# Brain1portA.net
KiCad netlist of a schematic drawn in EAGLE
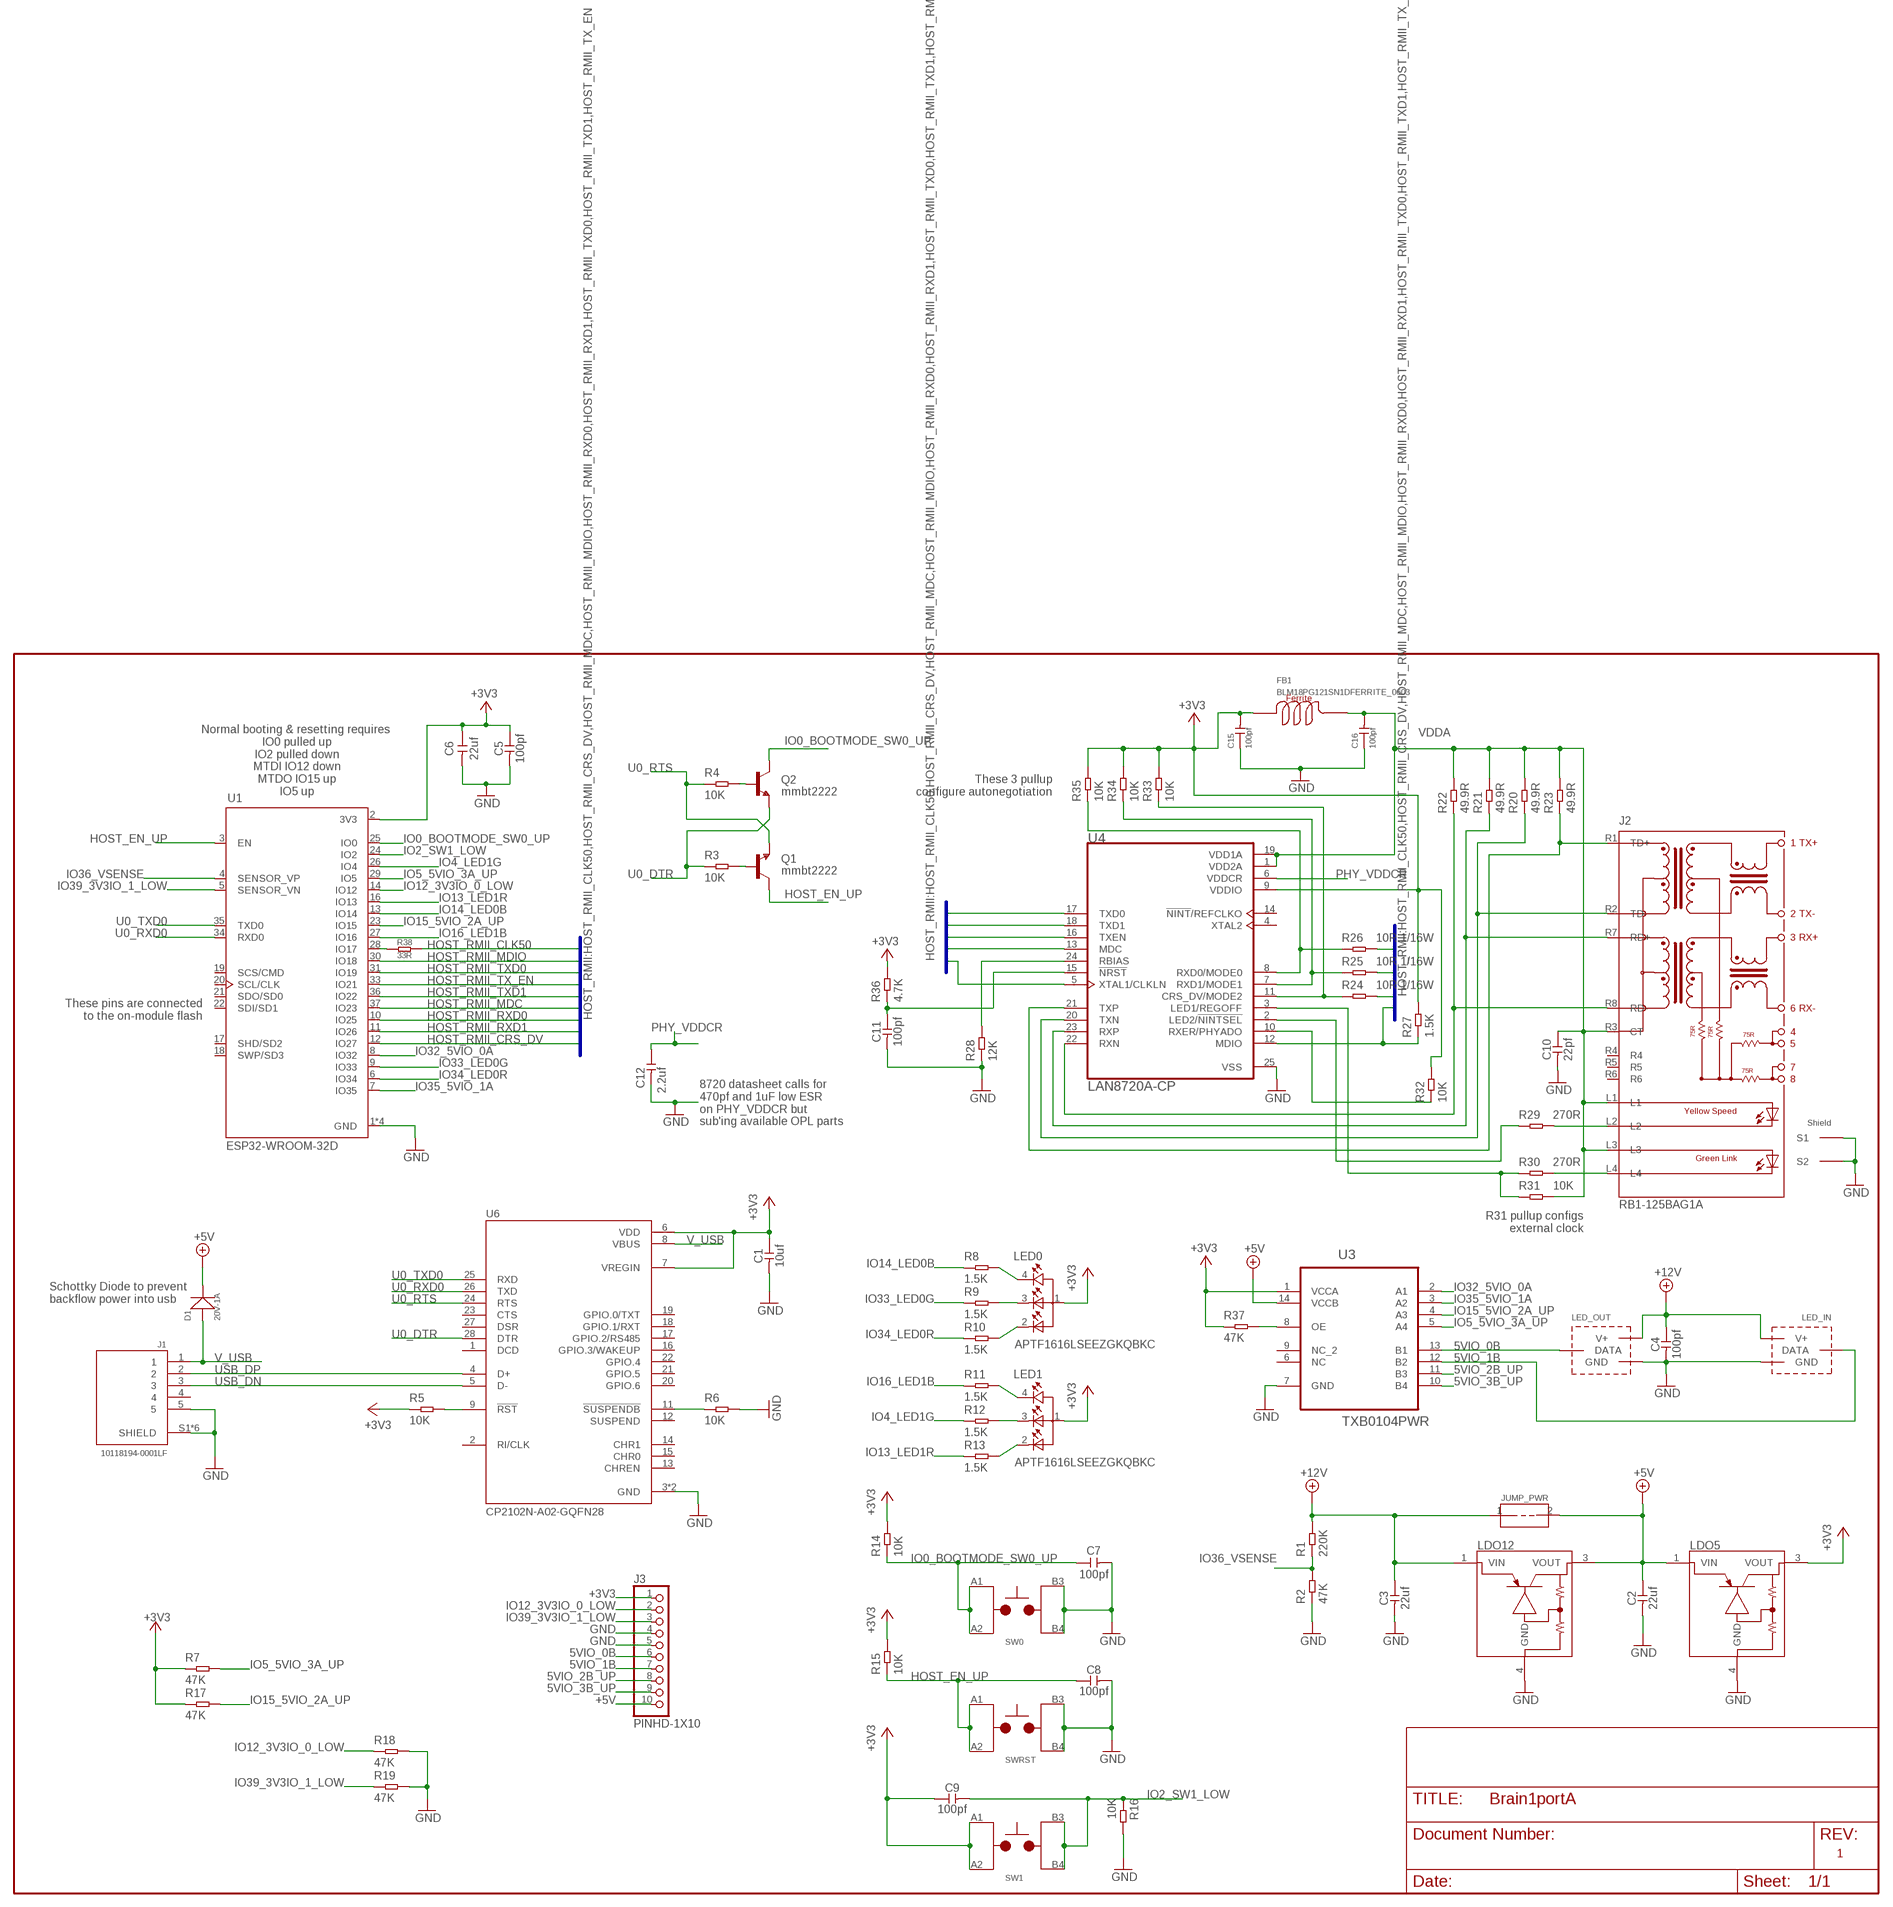
[diagram p0: schematic, sheet 1]

(export (version "E")
  (design (tool "Eeschema 10.0.6"))
  (components
    (comp (ref "C1")
      (value "10uf")
      (footprint "eagle-import:C0402")
      (fields (field (name "MPN") "CC0402MRX5R5BB106"))
      (libsource (lib "eagle-import") (part "CERAMIC-10UF-6.3V-20%-X5R(0402)"))
    )
    (comp (ref "C2")
      (value "22uf")
      (footprint "eagle-import:C0805")
      (fields (field (name "MPN") "CC0805MKX5R5BB226"))
      (libsource (lib "eagle-import") (part "CERAMIC-22UF-6.3V-20%-X5R(0805)"))
    )
    (comp (ref "C3")
      (value "22uf")
      (footprint "eagle-import:C0805")
      (fields (field (name "MPN") "CC0805MKX5R5BB226"))
      (libsource (lib "eagle-import") (part "CERAMIC-22UF-6.3V-20%-X5R(0805)"))
    )
    (comp (ref "C4")
      (value "100pf")
      (footprint "eagle-import:C0402")
      (fields (field (name "MPN") "CC0402JRNPO9BN101"))
      (libsource (lib "eagle-import") (part "CERAMIC-100PF-50V-5%-NPO(0402)"))
    )
    (comp (ref "C5")
      (value "100pf")
      (footprint "eagle-import:C0402")
      (fields (field (name "MPN") "CC0402JRNPO9BN101"))
      (libsource (lib "eagle-import") (part "CERAMIC-100PF-50V-5%-NPO(0402)"))
    )
    (comp (ref "C6")
      (value "22uf")
      (footprint "eagle-import:C0805")
      (fields (field (name "MPN") "CC0805MKX5R5BB226"))
      (libsource (lib "eagle-import") (part "CERAMIC-22UF-6.3V-20%-X5R(0805)"))
    )
    (comp (ref "C7")
      (value "100pf")
      (footprint "eagle-import:C0402")
      (fields (field (name "MPN") "CC0402JRNPO9BN101"))
      (libsource (lib "eagle-import") (part "CERAMIC-100PF-50V-5%-NPO(0402)"))
    )
    (comp (ref "C8")
      (value "100pf")
      (footprint "eagle-import:C0402")
      (fields (field (name "MPN") "CC0402JRNPO9BN101"))
      (libsource (lib "eagle-import") (part "CERAMIC-100PF-50V-5%-NPO(0402)"))
    )
    (comp (ref "C9")
      (value "100pf")
      (footprint "eagle-import:C0402")
      (fields (field (name "MPN") "CC0402JRNPO9BN101"))
      (libsource (lib "eagle-import") (part "CERAMIC-100PF-50V-5%-NPO(0402)"))
    )
    (comp (ref "C10")
      (value "22pf")
      (footprint "eagle-import:C0402")
      (fields (field (name "MPN") "CC0402JRNPO9BN220"))
      (libsource (lib "eagle-import") (part "CERAMIC-22PF-50V-5%-NPO(0402)"))
    )
    (comp (ref "C11")
      (value "100pf")
      (footprint "eagle-import:C0402")
      (fields (field (name "MPN") "CC0402JRNPO9BN101"))
      (libsource (lib "eagle-import") (part "CERAMIC-100PF-50V-5%-NPO(0402)"))
    )
    (comp (ref "C12")
      (value "2.2uf")
      (footprint "eagle-import:C0603")
      (fields (field (name "MPN") "CC0603KRX7R6BB225"))
      (libsource (lib "eagle-import") (part "CERAMIC-2.2UF-10V-10%-X7R(0603)"))
    )
    (comp (ref "C15")
      (value "100pf")
      (footprint "eagle-import:C0402")
      (fields (field (name "MPN") "CC0402JRNPO9BN101"))
      (libsource (lib "eagle-import") (part "CERAMIC-100PF-50V-5%-NPO(0402)"))
    )
    (comp (ref "C16")
      (value "100pf")
      (footprint "eagle-import:C0402")
      (fields (field (name "MPN") "CC0402JRNPO9BN101"))
      (libsource (lib "eagle-import") (part "CERAMIC-100PF-50V-5%-NPO(0402)"))
    )
    (comp (ref "D1")
      (value "20V-1A")
      (footprint "eagle-import:SOD-123")
      (fields (field (name "MPN") "B5819W"))
      (libsource (lib "eagle-import") (part "SMD-DIODE-SCHOTTKY-20V-1A(SOD-123)"))
    )
    (comp (ref "FB1")
      (value "BLM18PG121SN1DFERRITE_0603")
      (footprint "eagle-import:L0603")
      (libsource (lib "eagle-import") (part "BLM18PG121SN1DFERRITE_0603"))
    )
    (comp (ref "J1")
      (value "10118194-0001LF")
      (footprint "eagle-import:AMPHENOL_10118194-0001LF")
      (fields (field (name "DIGI-KEY_PART_NUMBER") "609-4618-1-ND") (field (name "MF") "Amphenol ICC"))
      (libsource (lib "eagle-import") (part "10118194-0001LF"))
    )
    (comp (ref "J2")
      (value "RB1-125BAG1A")
      (footprint "eagle-import:WIZNET_RB1-125BAG1A")
      (libsource (lib "eagle-import") (part "RB1-125BAG1A"))
    )
    (comp (ref "J3")
      (value "PINHD-1X10")
      (footprint "eagle-import:1X10-BIG")
      (libsource (lib "eagle-import") (part "PINHD-1X10"))
    )
    (comp (ref "JUMP_PWR")
      (value "PWR_SUPPLY_SHORT050_DRILLED")
      (footprint "eagle-import:SHORT_050_DRILLED")
      (libsource (lib "eagle-import") (part "PWR_SUPPLY_SHORT050_DRILLED"))
    )
    (comp (ref "LDO5")
      (value "NCP5501DPAK3")
      (footprint "eagle-import:TO229P990X238-3")
      (libsource (lib "eagle-import") (part "NCP5501DPAK3"))
    )
    (comp (ref "LDO12")
      (value "NCP5501DPAK3")
      (footprint "eagle-import:TO229P990X238-3")
      (libsource (lib "eagle-import") (part "NCP5501DPAK3"))
    )
    (comp (ref "LED0")
      (value "APTF1616LSEEZGKQBKC")
      (footprint "eagle-import:LEDSC160X160X070-4N")
      (fields (field (name "MF") "Kingbright"))
      (libsource (lib "eagle-import") (part "APTF1616LSEEZGKQBKC"))
    )
    (comp (ref "LED1")
      (value "APTF1616LSEEZGKQBKC")
      (footprint "eagle-import:LEDSC160X160X070-4N")
      (fields (field (name "MF") "Kingbright"))
      (libsource (lib "eagle-import") (part "APTF1616LSEEZGKQBKC"))
    )
    (comp (ref "LED_IN")
      (value "3WAY_LED_CONWIRES")
      (footprint "eagle-import:3WAY_LED_WIRES")
      (libsource (lib "eagle-import") (part "3WAY_LED_CONWIRES"))
    )
    (comp (ref "LED_OUT")
      (value "3WAY_LED_CONWIRES")
      (footprint "eagle-import:3WAY_LED_WIRES")
      (libsource (lib "eagle-import") (part "3WAY_LED_CONWIRES"))
    )
    (comp (ref "Q1")
      (value "mmbt2222")
      (footprint "eagle-import:SOT23-BEC")
      (libsource (lib "eagle-import") (part "-NPN-SOT23-BECMMBT2222ALT1"))
    )
    (comp (ref "Q2")
      (value "mmbt2222")
      (footprint "eagle-import:SOT23-BEC")
      (libsource (lib "eagle-import") (part "-NPN-SOT23-BECMMBT2222ALT1"))
    )
    (comp (ref "R1")
      (value "220K")
      (footprint "eagle-import:R0402")
      (fields (field (name "MPN") "RC0402JR-070RL"))
      (libsource (lib "eagle-import") (part "SMD-RES-220K-5%-1/16W(0402)"))
    )
    (comp (ref "R2")
      (value "47K")
      (footprint "eagle-import:R0402")
      (fields (field (name "MPN") "RC0402JR-0747KL"))
      (libsource (lib "eagle-import") (part "SMD-RES-47K-5%-1/16W(0402)"))
    )
    (comp (ref "R3")
      (value "10K")
      (footprint "eagle-import:R0402")
      (fields (field (name "MPN") "RC0402JR-0710KL"))
      (libsource (lib "eagle-import") (part "SMD-RES-10K-5%-1/(0402)"))
    )
    (comp (ref "R4")
      (value "10K")
      (footprint "eagle-import:R0402")
      (fields (field (name "MPN") "RC0402JR-0710KL"))
      (libsource (lib "eagle-import") (part "SMD-RES-10K-5%-1/(0402)"))
    )
    (comp (ref "R5")
      (value "10K")
      (footprint "eagle-import:R0402")
      (fields (field (name "MPN") "RC0402JR-0710KL"))
      (libsource (lib "eagle-import") (part "SMD-RES-10K-5%-1/(0402)"))
    )
    (comp (ref "R6")
      (value "10K")
      (footprint "eagle-import:R0402")
      (fields (field (name "MPN") "RC0402JR-0710KL"))
      (libsource (lib "eagle-import") (part "SMD-RES-10K-5%-1/(0402)"))
    )
    (comp (ref "R7")
      (value "47K")
      (footprint "eagle-import:R0402")
      (fields (field (name "MPN") "RC0402JR-0747KL"))
      (libsource (lib "eagle-import") (part "SMD-RES-47K-5%-1/16W(0402)"))
    )
    (comp (ref "R8")
      (value "1.5K")
      (footprint "eagle-import:R0402")
      (fields (field (name "MPN") "RC0402JR-071K5L"))
      (libsource (lib "eagle-import") (part "SMD-RES-1.5K-5%-1/16W(0402)"))
    )
    (comp (ref "R9")
      (value "1.5K")
      (footprint "eagle-import:R0402")
      (fields (field (name "MPN") "RC0402JR-071K5L"))
      (libsource (lib "eagle-import") (part "SMD-RES-1.5K-5%-1/16W(0402)"))
    )
    (comp (ref "R10")
      (value "1.5K")
      (footprint "eagle-import:R0402")
      (fields (field (name "MPN") "RC0402JR-071K5L"))
      (libsource (lib "eagle-import") (part "SMD-RES-1.5K-5%-1/16W(0402)"))
    )
    (comp (ref "R11")
      (value "1.5K")
      (footprint "eagle-import:R0402")
      (fields (field (name "MPN") "RC0402JR-071K5L"))
      (libsource (lib "eagle-import") (part "SMD-RES-1.5K-5%-1/16W(0402)"))
    )
    (comp (ref "R12")
      (value "1.5K")
      (footprint "eagle-import:R0402")
      (fields (field (name "MPN") "RC0402JR-071K5L"))
      (libsource (lib "eagle-import") (part "SMD-RES-1.5K-5%-1/16W(0402)"))
    )
    (comp (ref "R13")
      (value "1.5K")
      (footprint "eagle-import:R0402")
      (fields (field (name "MPN") "RC0402JR-071K5L"))
      (libsource (lib "eagle-import") (part "SMD-RES-1.5K-5%-1/16W(0402)"))
    )
    (comp (ref "R14")
      (value "10K")
      (footprint "eagle-import:R0402")
      (fields (field (name "MPN") "RC0402JR-0710KL"))
      (libsource (lib "eagle-import") (part "SMD-RES-10K-5%-1/(0402)"))
    )
    (comp (ref "R15")
      (value "10K")
      (footprint "eagle-import:R0402")
      (fields (field (name "MPN") "RC0402JR-0710KL"))
      (libsource (lib "eagle-import") (part "SMD-RES-10K-5%-1/(0402)"))
    )
    (comp (ref "R16")
      (value "10K")
      (footprint "eagle-import:R0402")
      (fields (field (name "MPN") "RC0402JR-0710KL"))
      (libsource (lib "eagle-import") (part "SMD-RES-10K-5%-1/(0402)"))
    )
    (comp (ref "R17")
      (value "47K")
      (footprint "eagle-import:R0402")
      (fields (field (name "MPN") "RC0402JR-0747KL"))
      (libsource (lib "eagle-import") (part "SMD-RES-47K-5%-1/16W(0402)"))
    )
    (comp (ref "R18")
      (value "47K")
      (footprint "eagle-import:R0402")
      (fields (field (name "MPN") "RC0402JR-0747KL"))
      (libsource (lib "eagle-import") (part "SMD-RES-47K-5%-1/16W(0402)"))
    )
    (comp (ref "R19")
      (value "47K")
      (footprint "eagle-import:R0402")
      (fields (field (name "MPN") "RC0402JR-0747KL"))
      (libsource (lib "eagle-import") (part "SMD-RES-47K-5%-1/16W(0402)"))
    )
    (comp (ref "R20")
      (value "49.9R")
      (footprint "eagle-import:R0402")
      (fields (field (name "MPN") "RC0402FR-0749R9L"))
      (libsource (lib "eagle-import") (part "SMD-RES-49.9R-1%-1/16W(0402)"))
    )
    (comp (ref "R21")
      (value "49.9R")
      (footprint "eagle-import:R0402")
      (fields (field (name "MPN") "RC0402FR-0749R9L"))
      (libsource (lib "eagle-import") (part "SMD-RES-49.9R-1%-1/16W(0402)"))
    )
    (comp (ref "R22")
      (value "49.9R")
      (footprint "eagle-import:R0402")
      (fields (field (name "MPN") "RC0402FR-0749R9L"))
      (libsource (lib "eagle-import") (part "SMD-RES-49.9R-1%-1/16W(0402)"))
    )
    (comp (ref "R23")
      (value "49.9R")
      (footprint "eagle-import:R0402")
      (fields (field (name "MPN") "RC0402FR-0749R9L"))
      (libsource (lib "eagle-import") (part "SMD-RES-49.9R-1%-1/16W(0402)"))
    )
    (comp (ref "R24")
      (value "10R 1/16W")
      (footprint "eagle-import:R0402")
      (fields (field (name "MPN") "RC0402JR-0710RL"))
      (libsource (lib "eagle-import") (part "SMD-RES-10R-5%-1/16W(0402)"))
    )
    (comp (ref "R25")
      (value "10R 1/16W")
      (footprint "eagle-import:R0402")
      (fields (field (name "MPN") "RC0402JR-0710RL"))
      (libsource (lib "eagle-import") (part "SMD-RES-10R-5%-1/16W(0402)"))
    )
    (comp (ref "R26")
      (value "10R 1/16W")
      (footprint "eagle-import:R0402")
      (fields (field (name "MPN") "RC0402JR-0710RL"))
      (libsource (lib "eagle-import") (part "SMD-RES-10R-5%-1/16W(0402)"))
    )
    (comp (ref "R27")
      (value "1.5K")
      (footprint "eagle-import:R0402")
      (fields (field (name "MPN") "RC0402JR-071K5L"))
      (libsource (lib "eagle-import") (part "SMD-RES-1.5K-5%-1/16W(0402)"))
    )
    (comp (ref "R28")
      (value "12K")
      (footprint "eagle-import:R0402")
      (fields (field (name "MPN") "RC0402JR-070RL"))
      (libsource (lib "eagle-import") (part "SMD-RES-12K-1%-1/16W(0402)"))
    )
    (comp (ref "R29")
      (value "270R")
      (footprint "eagle-import:R0402")
      (fields (field (name "MPN") "RC0402JR-070RL"))
      (libsource (lib "eagle-import") (part "SMD-RES-270R-1%-1/16W(0402)"))
    )
    (comp (ref "R30")
      (value "270R")
      (footprint "eagle-import:R0402")
      (fields (field (name "MPN") "RC0402JR-070RL"))
      (libsource (lib "eagle-import") (part "SMD-RES-270R-1%-1/16W(0402)"))
    )
    (comp (ref "R31")
      (value "10K")
      (footprint "eagle-import:R0402")
      (fields (field (name "MPN") "RC0402JR-0710KL"))
      (libsource (lib "eagle-import") (part "SMD-RES-10K-5%-1/(0402)"))
    )
    (comp (ref "R32")
      (value "10K")
      (footprint "eagle-import:R0402")
      (fields (field (name "MPN") "RC0402JR-0710KL"))
      (libsource (lib "eagle-import") (part "SMD-RES-10K-5%-1/(0402)"))
    )
    (comp (ref "R33")
      (value "10K")
      (footprint "eagle-import:R0402")
      (fields (field (name "MPN") "RC0402JR-0710KL"))
      (libsource (lib "eagle-import") (part "SMD-RES-10K-5%-1/(0402)"))
    )
    (comp (ref "R34")
      (value "10K")
      (footprint "eagle-import:R0402")
      (fields (field (name "MPN") "RC0402JR-0710KL"))
      (libsource (lib "eagle-import") (part "SMD-RES-10K-5%-1/(0402)"))
    )
    (comp (ref "R35")
      (value "10K")
      (footprint "eagle-import:R0402")
      (fields (field (name "MPN") "RC0402JR-0710KL"))
      (libsource (lib "eagle-import") (part "SMD-RES-10K-5%-1/(0402)"))
    )
    (comp (ref "R36")
      (value "4.7K")
      (footprint "eagle-import:R0402")
      (fields (field (name "MPN") "RC0402JR-074K7L"))
      (libsource (lib "eagle-import") (part "SMD-RES-4.7K-5%-1/16W(0402)"))
    )
    (comp (ref "R37")
      (value "47K")
      (footprint "eagle-import:R0402")
      (fields (field (name "MPN") "RC0402JR-0747KL"))
      (libsource (lib "eagle-import") (part "SMD-RES-47K-5%-1/16W(0402)"))
    )
    (comp (ref "R38")
      (value "33R")
      (footprint "eagle-import:R0603")
      (fields (field (name "MPN") "RC0603FR-071K5L"))
      (libsource (lib "eagle-import") (part "SMD-RES-33R-5%-1/10W(0603)"))
    )
    (comp (ref "SW0")
      (value "TL3301T3301SWITCH")
      (footprint "eagle-import:SW-4")
      (libsource (lib "eagle-import") (part "TL3301T3301SWITCH"))
    )
    (comp (ref "SW1")
      (value "TL3301T3301SWITCH")
      (footprint "eagle-import:SW-4")
      (libsource (lib "eagle-import") (part "TL3301T3301SWITCH"))
    )
    (comp (ref "SWRST")
      (value "TL3301T3301SWITCH")
      (footprint "eagle-import:SW-4")
      (libsource (lib "eagle-import") (part "TL3301T3301SWITCH"))
    )
    (comp (ref "U1")
      (value "ESP32-WROOM-32D")
      (footprint "eagle-import:MODULE_ESP32-WROOM-32D")
      (fields (field (name "DIGI-KEY_PART_NUMBER") "1904-1023-1-ND") (field (name "MF") "Espressif Systems"))
      (libsource (lib "eagle-import") (part "ESP32-WROOM-32D"))
    )
    (comp (ref "U3")
      (value "TXB0104PWR")
      (footprint "eagle-import:SOP65P640X120-14N")
      (fields (field (name "MF") "Texas Instruments"))
      (libsource (lib "eagle-import") (part "TXB0104PWR"))
    )
    (comp (ref "U4")
      (value "LAN8720A-CP")
      (footprint "eagle-import:QFN50P400X400X100-25N")
      (fields (field (name "DIGI-KEY_PART_NUMBER") "638-1080-ND") (field (name "MF") "Microchip"))
      (libsource (lib "eagle-import") (part "LAN8720A-CP"))
    )
    (comp (ref "U6")
      (value "CP2102N-A02-GQFN28")
      (footprint "eagle-import:QFN50P500X500X80-29N")
      (fields (field (name "MF") "Silicon Labs") (field (name "MP") "CP2102N-A01-GQFN28"))
      (libsource (lib "eagle-import") (part "CP2102N-A01-GQFN28"))
    )
  )
  (nets
    (net (code "2") (name "+3V3") (class "Default")
      (node (ref "C1") (pin "1") (pinfunction "1_1") (pintype "passive"))
      (node (ref "C15") (pin "2") (pinfunction "2_2") (pintype "passive"))
      (node (ref "C5") (pin "1") (pinfunction "1_1") (pintype "passive"))
      (node (ref "C6") (pin "1") (pinfunction "1_1") (pintype "passive"))
      (node (ref "C9") (pin "1") (pinfunction "1_1") (pintype "passive"))
      (node (ref "FB1") (pin "1") (pinfunction "P$1_1") (pintype "bidirectional"))
      (node (ref "J3") (pin "1") (pinfunction "1_1") (pintype "passive"))
      (node (ref "LDO5") (pin "3") (pinfunction "VOUT_3") (pintype "power_in"))
      (node (ref "LED0") (pin "1") (pinfunction "1_1") (pintype "passive"))
      (node (ref "LED1") (pin "1") (pinfunction "1_1") (pintype "passive"))
      (node (ref "R14") (pin "2") (pinfunction "2_2") (pintype "passive"))
      (node (ref "R15") (pin "2") (pinfunction "2_2") (pintype "passive"))
      (node (ref "R17") (pin "1") (pinfunction "1_1") (pintype "passive"))
      (node (ref "R27") (pin "2") (pinfunction "2_2") (pintype "passive"))
      (node (ref "R32") (pin "2") (pinfunction "2_2") (pintype "passive"))
      (node (ref "R33") (pin "2") (pinfunction "2_2") (pintype "passive"))
      (node (ref "R34") (pin "2") (pinfunction "2_2") (pintype "passive"))
      (node (ref "R35") (pin "2") (pinfunction "2_2") (pintype "passive"))
      (node (ref "R36") (pin "2") (pinfunction "2_2") (pintype "passive"))
      (node (ref "R37") (pin "1") (pinfunction "1_1") (pintype "passive"))
      (node (ref "R5") (pin "1") (pinfunction "1_1") (pintype "passive"))
      (node (ref "R7") (pin "1") (pinfunction "1_1") (pintype "passive"))
      (node (ref "SW1") (pin "A1") (pinfunction "1_A1") (pintype "bidirectional"))
      (node (ref "SW1") (pin "A2") (pinfunction "2_A2") (pintype "bidirectional"))
      (node (ref "U1") (pin "2") (pinfunction "3V3_2") (pintype "power_in"))
      (node (ref "U3") (pin "1") (pinfunction "VCCA_1") (pintype "power_in"))
      (node (ref "U4") (pin "9") (pinfunction "VDDIO_9") (pintype "power_in"))
      (node (ref "U6") (pin "6") (pinfunction "VDD_6") (pintype "power_in"))
      (node (ref "U6") (pin "7") (pinfunction "VREGIN_7") (pintype "power_in"))
    )
    (net (code "3") (name "+5V") (class "Default")
      (node (ref "C2") (pin "1") (pinfunction "1_1") (pintype "passive"))
      (node (ref "D1") (pin "-") (pinfunction "-_-") (pintype "passive"))
      (node (ref "J3") (pin "10") (pinfunction "10_10") (pintype "passive"))
      (node (ref "JUMP_PWR") (pin "2") (pinfunction "P$2_2") (pintype "bidirectional"))
      (node (ref "LDO12") (pin "3") (pinfunction "VOUT_3") (pintype "power_in"))
      (node (ref "LDO5") (pin "1") (pinfunction "VIN_1") (pintype "power_in"))
      (node (ref "U3") (pin "14") (pinfunction "VCCB_14") (pintype "power_in"))
    )
    (net (code "4") (name "+12V") (class "Default")
      (node (ref "C3") (pin "1") (pinfunction "1_1") (pintype "passive"))
      (node (ref "C4") (pin "1") (pinfunction "1_1") (pintype "passive"))
      (node (ref "JUMP_PWR") (pin "1") (pinfunction "P$1_1") (pintype "bidirectional"))
      (node (ref "LDO12") (pin "1") (pinfunction "VIN_1") (pintype "power_in"))
      (node (ref "LED_IN") (pin "V+") (pinfunction "V+_V+") (pintype "power_in"))
      (node (ref "LED_OUT") (pin "V+") (pinfunction "V+_V+") (pintype "power_in"))
      (node (ref "R1") (pin "2") (pinfunction "2_2") (pintype "passive"))
    )
    (net (code "5") (name "/5VIO_0B") (class "Default")
      (node (ref "J3") (pin "6") (pinfunction "6_6") (pintype "passive"))
      (node (ref "LED_OUT") (pin "DATA") (pinfunction "DATA_DATA") (pintype "bidirectional"))
      (node (ref "U3") (pin "13") (pinfunction "B1_13") (pintype "bidirectional"))
    )
    (net (code "6") (name "/5VIO_1B") (class "Default")
      (node (ref "J3") (pin "7") (pinfunction "7_7") (pintype "passive"))
      (node (ref "LED_IN") (pin "DATA") (pinfunction "DATA_DATA") (pintype "bidirectional"))
      (node (ref "U3") (pin "12") (pinfunction "B2_12") (pintype "bidirectional"))
    )
    (net (code "7") (name "/5VIO_2B_UP") (class "Default")
      (node (ref "J3") (pin "8") (pinfunction "8_8") (pintype "passive"))
      (node (ref "U3") (pin "11") (pinfunction "B3_11") (pintype "bidirectional"))
    )
    (net (code "8") (name "/5VIO_3B_UP") (class "Default")
      (node (ref "J3") (pin "9") (pinfunction "9_9") (pintype "passive"))
      (node (ref "U3") (pin "10") (pinfunction "B4_10") (pintype "bidirectional"))
    )
    (net (code "9") (name "/HOST_EN_UP") (class "Default")
      (node (ref "C8") (pin "1") (pinfunction "1_1") (pintype "passive"))
      (node (ref "Q1") (pin "C") (pinfunction "C_C") (pintype "passive"))
      (node (ref "R15") (pin "1") (pinfunction "1_1") (pintype "passive"))
      (node (ref "SWRST") (pin "A1") (pinfunction "1_A1") (pintype "bidirectional"))
      (node (ref "SWRST") (pin "A2") (pinfunction "2_A2") (pintype "bidirectional"))
      (node (ref "U1") (pin "3") (pinfunction "EN_3") (pintype "input"))
    )
    (net (code "10") (name "/HOST_RMII_CLK50") (class "Default")
      (node (ref "R38") (pin "2") (pinfunction "2_2") (pintype "passive"))
      (node (ref "U4") (pin "5") (pinfunction "XTAL1/CLKLN_5") (pintype "input"))
    )
    (net (code "11") (name "/HOST_RMII_CRS_DV") (class "Default")
      (node (ref "R24") (pin "2") (pinfunction "2_2") (pintype "passive"))
      (node (ref "U1") (pin "12") (pinfunction "IO27_12") (pintype "bidirectional"))
    )
    (net (code "12") (name "/HOST_RMII_MDC") (class "Default")
      (node (ref "U1") (pin "37") (pinfunction "IO23_37") (pintype "bidirectional"))
      (node (ref "U4") (pin "13") (pinfunction "MDC_13") (pintype "input"))
    )
    (net (code "13") (name "/HOST_RMII_MDIO") (class "Default")
      (node (ref "R27") (pin "1") (pinfunction "1_1") (pintype "passive"))
      (node (ref "U1") (pin "30") (pinfunction "IO18_30") (pintype "bidirectional"))
      (node (ref "U4") (pin "12") (pinfunction "MDIO_12") (pintype "bidirectional"))
    )
    (net (code "14") (name "/HOST_RMII_RXD0") (class "Default")
      (node (ref "R26") (pin "2") (pinfunction "2_2") (pintype "passive"))
      (node (ref "U1") (pin "10") (pinfunction "IO25_10") (pintype "bidirectional"))
    )
    (net (code "15") (name "/HOST_RMII_RXD1") (class "Default")
      (node (ref "R25") (pin "2") (pinfunction "2_2") (pintype "passive"))
      (node (ref "U1") (pin "11") (pinfunction "IO26_11") (pintype "bidirectional"))
    )
    (net (code "16") (name "/HOST_RMII_TXD0") (class "Default")
      (node (ref "U1") (pin "31") (pinfunction "IO19_31") (pintype "bidirectional"))
      (node (ref "U4") (pin "17") (pinfunction "TXD0_17") (pintype "input"))
    )
    (net (code "17") (name "/HOST_RMII_TXD1") (class "Default")
      (node (ref "U1") (pin "36") (pinfunction "IO22_36") (pintype "bidirectional"))
      (node (ref "U4") (pin "18") (pinfunction "TXD1_18") (pintype "input"))
    )
    (net (code "18") (name "/HOST_RMII_TX_EN") (class "Default")
      (node (ref "U1") (pin "33") (pinfunction "IO21_33") (pintype "bidirectional"))
      (node (ref "U4") (pin "16") (pinfunction "TXEN_16") (pintype "input"))
    )
    (net (code "19") (name "/IO0_BOOTMODE_SW0_UP") (class "Default")
      (node (ref "C7") (pin "1") (pinfunction "1_1") (pintype "passive"))
      (node (ref "Q2") (pin "C") (pinfunction "C_C") (pintype "passive"))
      (node (ref "R14") (pin "1") (pinfunction "1_1") (pintype "passive"))
      (node (ref "SW0") (pin "A1") (pinfunction "1_A1") (pintype "bidirectional"))
      (node (ref "SW0") (pin "A2") (pinfunction "2_A2") (pintype "bidirectional"))
      (node (ref "U1") (pin "25") (pinfunction "IO0_25") (pintype "bidirectional"))
    )
    (net (code "20") (name "/IO2_SW1_LOW") (class "Default")
      (node (ref "C9") (pin "2") (pinfunction "2_2") (pintype "passive"))
      (node (ref "R16") (pin "1") (pinfunction "1_1") (pintype "passive"))
      (node (ref "SW1") (pin "B3") (pinfunction "3_B3") (pintype "bidirectional"))
      (node (ref "SW1") (pin "B4") (pinfunction "4_B4") (pintype "bidirectional"))
      (node (ref "U1") (pin "24") (pinfunction "IO2_24") (pintype "bidirectional"))
    )
    (net (code "21") (name "/IO4_LED1G") (class "Default")
      (node (ref "R12") (pin "1") (pinfunction "1_1") (pintype "passive"))
      (node (ref "U1") (pin "26") (pinfunction "IO4_26") (pintype "bidirectional"))
    )
    (net (code "22") (name "/IO5_5VIO_3A_UP") (class "Default")
      (node (ref "R7") (pin "2") (pinfunction "2_2") (pintype "passive"))
      (node (ref "U1") (pin "29") (pinfunction "IO5_29") (pintype "bidirectional"))
      (node (ref "U3") (pin "5") (pinfunction "A4_5") (pintype "bidirectional"))
    )
    (net (code "23") (name "/IO12_3V3IO_0_LOW") (class "Default")
      (node (ref "J3") (pin "2") (pinfunction "2_2") (pintype "passive"))
      (node (ref "R18") (pin "1") (pinfunction "1_1") (pintype "passive"))
      (node (ref "U1") (pin "14") (pinfunction "IO12_14") (pintype "bidirectional"))
    )
    (net (code "24") (name "/IO13_LED1R") (class "Default")
      (node (ref "R13") (pin "1") (pinfunction "1_1") (pintype "passive"))
      (node (ref "U1") (pin "16") (pinfunction "IO13_16") (pintype "bidirectional"))
    )
    (net (code "25") (name "/IO14_LED0B") (class "Default")
      (node (ref "R8") (pin "1") (pinfunction "1_1") (pintype "passive"))
      (node (ref "U1") (pin "13") (pinfunction "IO14_13") (pintype "bidirectional"))
    )
    (net (code "26") (name "/IO15_5VIO_2A_UP") (class "Default")
      (node (ref "R17") (pin "2") (pinfunction "2_2") (pintype "passive"))
      (node (ref "U1") (pin "23") (pinfunction "IO15_23") (pintype "bidirectional"))
      (node (ref "U3") (pin "4") (pinfunction "A3_4") (pintype "bidirectional"))
    )
    (net (code "27") (name "/IO16_LED1B") (class "Default")
      (node (ref "R11") (pin "1") (pinfunction "1_1") (pintype "passive"))
      (node (ref "U1") (pin "27") (pinfunction "IO16_27") (pintype "bidirectional"))
    )
    (net (code "28") (name "/IO32_5VIO_0A") (class "Default")
      (node (ref "U1") (pin "8") (pinfunction "IO32_8") (pintype "bidirectional"))
      (node (ref "U3") (pin "2") (pinfunction "A1_2") (pintype "bidirectional"))
    )
    (net (code "29") (name "/IO33_LED0G") (class "Default")
      (node (ref "R9") (pin "1") (pinfunction "1_1") (pintype "passive"))
      (node (ref "U1") (pin "9") (pinfunction "IO33_9") (pintype "bidirectional"))
    )
    (net (code "30") (name "/IO34_LED0R") (class "Default")
      (node (ref "R10") (pin "1") (pinfunction "1_1") (pintype "passive"))
      (node (ref "U1") (pin "6") (pinfunction "IO34_6") (pintype "bidirectional"))
    )
    (net (code "31") (name "/IO35_5VIO_1A") (class "Default")
      (node (ref "U1") (pin "7") (pinfunction "IO35_7") (pintype "bidirectional"))
      (node (ref "U3") (pin "3") (pinfunction "A2_3") (pintype "bidirectional"))
    )
    (net (code "32") (name "/IO36_VSENSE") (class "Default")
      (node (ref "R1") (pin "1") (pinfunction "1_1") (pintype "passive"))
      (node (ref "R2") (pin "2") (pinfunction "2_2") (pintype "passive"))
      (node (ref "U1") (pin "4") (pinfunction "SENSOR_VP_4") (pintype "input"))
    )
    (net (code "33") (name "/IO39_3V3IO_1_LOW") (class "Default")
      (node (ref "J3") (pin "3") (pinfunction "3_3") (pintype "passive"))
      (node (ref "R19") (pin "1") (pinfunction "1_1") (pintype "passive"))
      (node (ref "U1") (pin "5") (pinfunction "SENSOR_VN_5") (pintype "input"))
    )
    (net (code "34") (name "/PHY_VDDCR") (class "Default")
      (node (ref "C12") (pin "1") (pinfunction "1_1") (pintype "passive"))
      (node (ref "U4") (pin "6") (pinfunction "VDDCR_6") (pintype "power_in"))
    )
    (net (code "35") (name "/U0_DTR") (class "Default")
      (node (ref "Q2") (pin "E") (pinfunction "E_E") (pintype "passive"))
      (node (ref "R3") (pin "1") (pinfunction "1_1") (pintype "passive"))
      (node (ref "U6") (pin "28") (pinfunction "DTR_28") (pintype "output"))
    )
    (net (code "36") (name "/U0_RTS") (class "Default")
      (node (ref "Q1") (pin "E") (pinfunction "E_E") (pintype "passive"))
      (node (ref "R4") (pin "1") (pinfunction "1_1") (pintype "passive"))
      (node (ref "U6") (pin "24") (pinfunction "RTS_24") (pintype "output"))
    )
    (net (code "37") (name "/U0_RXD0") (class "Default")
      (node (ref "U1") (pin "34") (pinfunction "RXD0_34") (pintype "bidirectional"))
      (node (ref "U6") (pin "26") (pinfunction "TXD_26") (pintype "output"))
    )
    (net (code "38") (name "/U0_TXD0") (class "Default")
      (node (ref "U1") (pin "35") (pinfunction "TXD0_35") (pintype "bidirectional"))
      (node (ref "U6") (pin "25") (pinfunction "RXD_25") (pintype "input"))
    )
    (net (code "39") (name "/USB_DN") (class "Default")
      (node (ref "J1") (pin "3") (pinfunction "3_3") (pintype "passive"))
      (node (ref "U6") (pin "5") (pinfunction "D-_5") (pintype "bidirectional"))
    )
    (net (code "40") (name "/USB_DP") (class "Default")
      (node (ref "J1") (pin "2") (pinfunction "2_2") (pintype "passive"))
      (node (ref "U6") (pin "4") (pinfunction "D+_4") (pintype "bidirectional"))
    )
    (net (code "41") (name "/VDDA") (class "Default")
      (node (ref "C10") (pin "1") (pinfunction "1_1") (pintype "passive"))
      (node (ref "C16") (pin "2") (pinfunction "2_2") (pintype "passive"))
      (node (ref "FB1") (pin "2") (pinfunction "P$2_2") (pintype "bidirectional"))
      (node (ref "J2") (pin "L1") (pinfunction "L1_L1") (pintype "passive"))
      (node (ref "J2") (pin "L3") (pinfunction "L3_L3") (pintype "passive"))
      (node (ref "J2") (pin "R3") (pinfunction "CT_R3") (pintype "input"))
      (node (ref "R20") (pin "2") (pinfunction "2_2") (pintype "passive"))
      (node (ref "R21") (pin "2") (pinfunction "2_2") (pintype "passive"))
      (node (ref "R22") (pin "2") (pinfunction "2_2") (pintype "passive"))
      (node (ref "R23") (pin "2") (pinfunction "2_2") (pintype "passive"))
      (node (ref "R31") (pin "2") (pinfunction "2_2") (pintype "passive"))
      (node (ref "U4") (pin "1") (pinfunction "VDD2A_1") (pintype "power_in"))
      (node (ref "U4") (pin "19") (pinfunction "VDD1A_19") (pintype "power_in"))
    )
    (net (code "42") (name "/V_USB") (class "Default")
      (node (ref "D1") (pin "+") (pinfunction "+_+") (pintype "passive"))
      (node (ref "J1") (pin "1") (pinfunction "1_1") (pintype "passive"))
      (node (ref "U6") (pin "8") (pinfunction "VBUS_8") (pintype "power_in"))
    )
    (net (code "44") (name "GND") (class "Default")
      (node (ref "C1") (pin "2") (pinfunction "2_2") (pintype "passive"))
      (node (ref "C10") (pin "2") (pinfunction "2_2") (pintype "passive"))
      (node (ref "C11") (pin "2") (pinfunction "2_2") (pintype "passive"))
      (node (ref "C12") (pin "2") (pinfunction "2_2") (pintype "passive"))
      (node (ref "C15") (pin "1") (pinfunction "1_1") (pintype "passive"))
      (node (ref "C16") (pin "1") (pinfunction "1_1") (pintype "passive"))
      (node (ref "C2") (pin "2") (pinfunction "2_2") (pintype "passive"))
      (node (ref "C3") (pin "2") (pinfunction "2_2") (pintype "passive"))
      (node (ref "C4") (pin "2") (pinfunction "2_2") (pintype "passive"))
      (node (ref "C5") (pin "2") (pinfunction "2_2") (pintype "passive"))
      (node (ref "C6") (pin "2") (pinfunction "2_2") (pintype "passive"))
      (node (ref "C7") (pin "2") (pinfunction "2_2") (pintype "passive"))
      (node (ref "C8") (pin "2") (pinfunction "2_2") (pintype "passive"))
      (node (ref "J1") (pin "5") (pinfunction "5_5") (pintype "passive"))
      (node (ref "J1") (pin "S1") (pinfunction "SHIELD_S1") (pintype "passive"))
      (node (ref "J1") (pin "S2") (pinfunction "SHIELD_S2") (pintype "passive"))
      (node (ref "J1") (pin "S3") (pinfunction "SHIELD_S3") (pintype "passive"))
      (node (ref "J1") (pin "S4") (pinfunction "SHIELD_S4") (pintype "passive"))
      (node (ref "J1") (pin "S5") (pinfunction "SHIELD_S5") (pintype "passive"))
      (node (ref "J1") (pin "S6") (pinfunction "SHIELD_S6") (pintype "passive"))
      (node (ref "J2") (pin "S1") (pinfunction "S1_S1") (pintype "power_in"))
      (node (ref "J2") (pin "S2") (pinfunction "S2_S2") (pintype "power_in"))
      (node (ref "J3") (pin "4") (pinfunction "4_4") (pintype "passive"))
      (node (ref "J3") (pin "5") (pinfunction "5_5") (pintype "passive"))
      (node (ref "LDO12") (pin "4") (pinfunction "GND_4") (pintype "power_in"))
      (node (ref "LDO5") (pin "4") (pinfunction "GND_4") (pintype "power_in"))
      (node (ref "LED_IN") (pin "GND") (pinfunction "GND_GND") (pintype "power_in"))
      (node (ref "LED_OUT") (pin "GND") (pinfunction "GND_GND") (pintype "power_in"))
      (node (ref "R16") (pin "2") (pinfunction "2_2") (pintype "passive"))
      (node (ref "R18") (pin "2") (pinfunction "2_2") (pintype "passive"))
      (node (ref "R19") (pin "2") (pinfunction "2_2") (pintype "passive"))
      (node (ref "R2") (pin "1") (pinfunction "1_1") (pintype "passive"))
      (node (ref "R28") (pin "1") (pinfunction "1_1") (pintype "passive"))
      (node (ref "R6") (pin "2") (pinfunction "2_2") (pintype "passive"))
      (node (ref "SW0") (pin "B3") (pinfunction "3_B3") (pintype "bidirectional"))
      (node (ref "SW0") (pin "B4") (pinfunction "4_B4") (pintype "bidirectional"))
      (node (ref "SWRST") (pin "B3") (pinfunction "3_B3") (pintype "bidirectional"))
      (node (ref "SWRST") (pin "B4") (pinfunction "4_B4") (pintype "bidirectional"))
      (node (ref "U1") (pin "1") (pinfunction "GND_1") (pintype "power_in"))
      (node (ref "U1") (pin "15") (pinfunction "GND_15") (pintype "power_in"))
      (node (ref "U1") (pin "38") (pinfunction "GND_38") (pintype "power_in"))
      (node (ref "U1") (pin "39") (pinfunction "GND_39") (pintype "power_in"))
      (node (ref "U3") (pin "7") (pinfunction "GND_7") (pintype "passive"))
      (node (ref "U4") (pin "25") (pinfunction "VSS_25") (pintype "power_in"))
      (node (ref "U6") (pin "29") (pinfunction "GND_29") (pintype "power_in"))
      (node (ref "U6") (pin "3") (pinfunction "GND_3") (pintype "power_in"))
    )
    (net (code "45") (name "Net-(J2-PadL2)") (class "Default")
      (node (ref "J2") (pin "L2") (pinfunction "L2_L2") (pintype "passive"))
      (node (ref "R29") (pin "2") (pinfunction "2_2") (pintype "passive"))
    )
    (net (code "46") (name "Net-(J2-PadL4)") (class "Default")
      (node (ref "J2") (pin "L4") (pinfunction "L4_L4") (pintype "passive"))
      (node (ref "R30") (pin "2") (pinfunction "2_2") (pintype "passive"))
    )
    (net (code "47") (name "Net-(J2-RD+)") (class "Default")
      (node (ref "J2") (pin "R7") (pinfunction "RD+_R7") (pintype "input"))
      (node (ref "R21") (pin "1") (pinfunction "1_1") (pintype "passive"))
      (node (ref "U4") (pin "23") (pinfunction "RXP_23") (pintype "bidirectional"))
    )
    (net (code "48") (name "Net-(J2-RD-)") (class "Default")
      (node (ref "J2") (pin "R8") (pinfunction "RD-_R8") (pintype "input"))
      (node (ref "R22") (pin "1") (pinfunction "1_1") (pintype "passive"))
      (node (ref "U4") (pin "22") (pinfunction "RXN_22") (pintype "bidirectional"))
    )
    (net (code "49") (name "Net-(J2-TD+)") (class "Default")
      (node (ref "J2") (pin "R1") (pinfunction "TD+_R1") (pintype "input"))
      (node (ref "R23") (pin "1") (pinfunction "1_1") (pintype "passive"))
      (node (ref "U4") (pin "21") (pinfunction "TXP_21") (pintype "bidirectional"))
    )
    (net (code "50") (name "Net-(J2-TD-)") (class "Default")
      (node (ref "J2") (pin "R2") (pinfunction "TD-_R2") (pintype "input"))
      (node (ref "R20") (pin "1") (pinfunction "1_1") (pintype "passive"))
      (node (ref "U4") (pin "20") (pinfunction "TXN_20") (pintype "bidirectional"))
    )
    (net (code "51") (name "Net-(LED0-Pad2)") (class "Default")
      (node (ref "LED0") (pin "2") (pinfunction "2_2") (pintype "passive"))
      (node (ref "R10") (pin "2") (pinfunction "2_2") (pintype "passive"))
    )
    (net (code "52") (name "Net-(LED0-Pad3)") (class "Default")
      (node (ref "LED0") (pin "3") (pinfunction "3_3") (pintype "passive"))
      (node (ref "R9") (pin "2") (pinfunction "2_2") (pintype "passive"))
    )
    (net (code "53") (name "Net-(LED0-Pad4)") (class "Default")
      (node (ref "LED0") (pin "4") (pinfunction "4_4") (pintype "passive"))
      (node (ref "R8") (pin "2") (pinfunction "2_2") (pintype "passive"))
    )
    (net (code "54") (name "Net-(LED1-Pad2)") (class "Default")
      (node (ref "LED1") (pin "2") (pinfunction "2_2") (pintype "passive"))
      (node (ref "R13") (pin "2") (pinfunction "2_2") (pintype "passive"))
    )
    (net (code "55") (name "Net-(LED1-Pad3)") (class "Default")
      (node (ref "LED1") (pin "3") (pinfunction "3_3") (pintype "passive"))
      (node (ref "R12") (pin "2") (pinfunction "2_2") (pintype "passive"))
    )
    (net (code "56") (name "Net-(LED1-Pad4)") (class "Default")
      (node (ref "LED1") (pin "4") (pinfunction "4_4") (pintype "passive"))
      (node (ref "R11") (pin "2") (pinfunction "2_2") (pintype "passive"))
    )
    (net (code "57") (name "Net-(Q1-PadB)") (class "Default")
      (node (ref "Q1") (pin "B") (pinfunction "B_B") (pintype "passive"))
      (node (ref "R3") (pin "2") (pinfunction "2_2") (pintype "passive"))
    )
    (net (code "58") (name "Net-(Q2-PadB)") (class "Default")
      (node (ref "Q2") (pin "B") (pinfunction "B_B") (pintype "passive"))
      (node (ref "R4") (pin "2") (pinfunction "2_2") (pintype "passive"))
    )
    (net (code "59") (name "Net-(U1-IO17)") (class "Default")
      (node (ref "R38") (pin "1") (pinfunction "1_1") (pintype "passive"))
      (node (ref "U1") (pin "28") (pinfunction "IO17_28") (pintype "bidirectional"))
    )
    (net (code "60") (name "Net-(U3-OE)") (class "Default")
      (node (ref "R37") (pin "2") (pinfunction "2_2") (pintype "passive"))
      (node (ref "U3") (pin "8") (pinfunction "OE_8") (pintype "input"))
    )
    (net (code "61") (name "Net-(U4-CRS_DV{slash}MODE2)") (class "Default")
      (node (ref "R24") (pin "1") (pinfunction "1_1") (pintype "passive"))
      (node (ref "R33") (pin "1") (pinfunction "1_1") (pintype "passive"))
      (node (ref "U4") (pin "11") (pinfunction "CRS_DV/MODE2_11") (pintype "bidirectional"))
    )
    (net (code "62") (name "Net-(U4-LED1{slash}REGOFF)") (class "Default")
      (node (ref "R30") (pin "1") (pinfunction "1_1") (pintype "passive"))
      (node (ref "R31") (pin "1") (pinfunction "1_1") (pintype "passive"))
      (node (ref "U4") (pin "3") (pinfunction "LED1/REGOFF_3") (pintype "bidirectional"))
    )
    (net (code "63") (name "Net-(U4-LED2{slash}~{NINTSEL})") (class "Default")
      (node (ref "R29") (pin "1") (pinfunction "1_1") (pintype "passive"))
      (node (ref "U4") (pin "2") (pinfunction "LED2/~{NINTSEL}_2") (pintype "bidirectional"))
    )
    (net (code "64") (name "Net-(U4-RBIAS)") (class "Default")
      (node (ref "R28") (pin "2") (pinfunction "2_2") (pintype "passive"))
      (node (ref "U4") (pin "24") (pinfunction "RBIAS_24") (pintype "input"))
    )
    (net (code "65") (name "Net-(U4-RXD0{slash}MODE0)") (class "Default")
      (node (ref "R26") (pin "1") (pinfunction "1_1") (pintype "passive"))
      (node (ref "R35") (pin "1") (pinfunction "1_1") (pintype "passive"))
      (node (ref "U4") (pin "8") (pinfunction "RXD0/MODE0_8") (pintype "bidirectional"))
    )
    (net (code "66") (name "Net-(U4-RXD1{slash}MODE1)") (class "Default")
      (node (ref "R25") (pin "1") (pinfunction "1_1") (pintype "passive"))
      (node (ref "R34") (pin "1") (pinfunction "1_1") (pintype "passive"))
      (node (ref "U4") (pin "7") (pinfunction "RXD1/MODE1_7") (pintype "bidirectional"))
    )
    (net (code "67") (name "Net-(U4-RXER{slash}PHYADO)") (class "Default")
      (node (ref "R32") (pin "1") (pinfunction "1_1") (pintype "passive"))
      (node (ref "U4") (pin "10") (pinfunction "RXER/PHYADO_10") (pintype "bidirectional"))
    )
    (net (code "68") (name "Net-(U4-~{NRST})") (class "Default")
      (node (ref "C11") (pin "1") (pinfunction "1_1") (pintype "passive"))
      (node (ref "R36") (pin "1") (pinfunction "1_1") (pintype "passive"))
      (node (ref "U4") (pin "15") (pinfunction "~{NRST}_15") (pintype "input"))
    )
    (net (code "69") (name "Net-(U6-~{RST})") (class "Default")
      (node (ref "R5") (pin "2") (pinfunction "2_2") (pintype "passive"))
      (node (ref "U6") (pin "9") (pinfunction "~{RST}_9") (pintype "input"))
    )
    (net (code "70") (name "Net-(U6-~{SUSPENDB})") (class "Default")
      (node (ref "R6") (pin "1") (pinfunction "1_1") (pintype "passive"))
      (node (ref "U6") (pin "11") (pinfunction "~{SUSPENDB}_11") (pintype "output"))
    )
    (net (code "71") (name "unconnected-(J1-Pad4)") (class "Default")
      (node (ref "J1") (pin "4") (pinfunction "4_4") (pintype "passive"))
    )
    (net (code "72") (name "unconnected-(J2-PadR4)") (class "Default")
      (node (ref "J2") (pin "R4") (pinfunction "R4_R4") (pintype "input"))
    )
    (net (code "73") (name "unconnected-(J2-PadR5)") (class "Default")
      (node (ref "J2") (pin "R5") (pinfunction "R5_R5") (pintype "input"))
    )
    (net (code "74") (name "unconnected-(J2-PadR6)") (class "Default")
      (node (ref "J2") (pin "R6") (pinfunction "R6_R6") (pintype "input"))
    )
    (net (code "75") (name "unconnected-(U1-SCL{slash}CLK-Pad20)") (class "Default")
      (node (ref "U1") (pin "20") (pinfunction "SCL/CLK_20") (pintype "bidirectional"))
    )
    (net (code "76") (name "unconnected-(U1-SCS{slash}CMD-Pad19)") (class "Default")
      (node (ref "U1") (pin "19") (pinfunction "SCS/CMD_19") (pintype "bidirectional"))
    )
    (net (code "77") (name "unconnected-(U1-SDI{slash}SD1-Pad22)") (class "Default")
      (node (ref "U1") (pin "22") (pinfunction "SDI/SD1_22") (pintype "bidirectional"))
    )
    (net (code "78") (name "unconnected-(U1-SDO{slash}SD0-Pad21)") (class "Default")
      (node (ref "U1") (pin "21") (pinfunction "SDO/SD0_21") (pintype "bidirectional"))
    )
    (net (code "79") (name "unconnected-(U1-SHD{slash}SD2-Pad17)") (class "Default")
      (node (ref "U1") (pin "17") (pinfunction "SHD/SD2_17") (pintype "bidirectional"))
    )
    (net (code "80") (name "unconnected-(U1-SWP{slash}SD3-Pad18)") (class "Default")
      (node (ref "U1") (pin "18") (pinfunction "SWP/SD3_18") (pintype "bidirectional"))
    )
    (net (code "81") (name "unconnected-(U3-NC-Pad6)") (class "Default")
      (node (ref "U3") (pin "6") (pinfunction "NC_6") (pintype "no_connect"))
    )
    (net (code "82") (name "unconnected-(U3-NC_2-Pad9)") (class "Default")
      (node (ref "U3") (pin "9") (pinfunction "NC_2_9") (pintype "no_connect"))
    )
    (net (code "83") (name "unconnected-(U4-XTAL2-Pad4)") (class "Default")
      (node (ref "U4") (pin "4") (pinfunction "XTAL2_4") (pintype "output"))
    )
    (net (code "84") (name "unconnected-(U4-~{NINT}{slash}REFCLKO-Pad14)") (class "Default")
      (node (ref "U4") (pin "14") (pinfunction "~{NINT}/REFCLKO_14") (pintype "output"))
    )
    (net (code "85") (name "unconnected-(U6-CHR0-Pad15)") (class "Default")
      (node (ref "U6") (pin "15") (pinfunction "CHR0_15") (pintype "output"))
    )
    (net (code "86") (name "unconnected-(U6-CHR1-Pad14)") (class "Default")
      (node (ref "U6") (pin "14") (pinfunction "CHR1_14") (pintype "output"))
    )
    (net (code "87") (name "unconnected-(U6-CHREN-Pad13)") (class "Default")
      (node (ref "U6") (pin "13") (pinfunction "CHREN_13") (pintype "output"))
    )
    (net (code "88") (name "unconnected-(U6-CTS-Pad23)") (class "Default")
      (node (ref "U6") (pin "23") (pinfunction "CTS_23") (pintype "input"))
    )
    (net (code "89") (name "unconnected-(U6-DCD-Pad1)") (class "Default")
      (node (ref "U6") (pin "1") (pinfunction "DCD_1") (pintype "input"))
    )
    (net (code "90") (name "unconnected-(U6-DSR-Pad27)") (class "Default")
      (node (ref "U6") (pin "27") (pinfunction "DSR_27") (pintype "input"))
    )
    (net (code "91") (name "unconnected-(U6-GPIO.0{slash}TXT-Pad19)") (class "Default")
      (node (ref "U6") (pin "19") (pinfunction "GPIO.0/TXT_19") (pintype "bidirectional"))
    )
    (net (code "92") (name "unconnected-(U6-GPIO.1{slash}RXT-Pad18)") (class "Default")
      (node (ref "U6") (pin "18") (pinfunction "GPIO.1/RXT_18") (pintype "bidirectional"))
    )
    (net (code "93") (name "unconnected-(U6-GPIO.2{slash}RS485-Pad17)") (class "Default")
      (node (ref "U6") (pin "17") (pinfunction "GPIO.2/RS485_17") (pintype "bidirectional"))
    )
    (net (code "94") (name "unconnected-(U6-GPIO.3{slash}WAKEUP-Pad16)") (class "Default")
      (node (ref "U6") (pin "16") (pinfunction "GPIO.3/WAKEUP_16") (pintype "bidirectional"))
    )
    (net (code "95") (name "unconnected-(U6-GPIO.4-Pad22)") (class "Default")
      (node (ref "U6") (pin "22") (pinfunction "GPIO.4_22") (pintype "bidirectional"))
    )
    (net (code "96") (name "unconnected-(U6-GPIO.5-Pad21)") (class "Default")
      (node (ref "U6") (pin "21") (pinfunction "GPIO.5_21") (pintype "bidirectional"))
    )
    (net (code "97") (name "unconnected-(U6-GPIO.6-Pad20)") (class "Default")
      (node (ref "U6") (pin "20") (pinfunction "GPIO.6_20") (pintype "bidirectional"))
    )
    (net (code "98") (name "unconnected-(U6-RI{slash}CLK-Pad2)") (class "Default")
      (node (ref "U6") (pin "2") (pinfunction "RI/CLK_2") (pintype "bidirectional"))
    )
    (net (code "99") (name "unconnected-(U6-SUSPEND-Pad12)") (class "Default")
      (node (ref "U6") (pin "12") (pinfunction "SUSPEND_12") (pintype "output"))
    )
  )
)
